# nuc120.net
KiCad netlist of a schematic drawn in Altium Designer
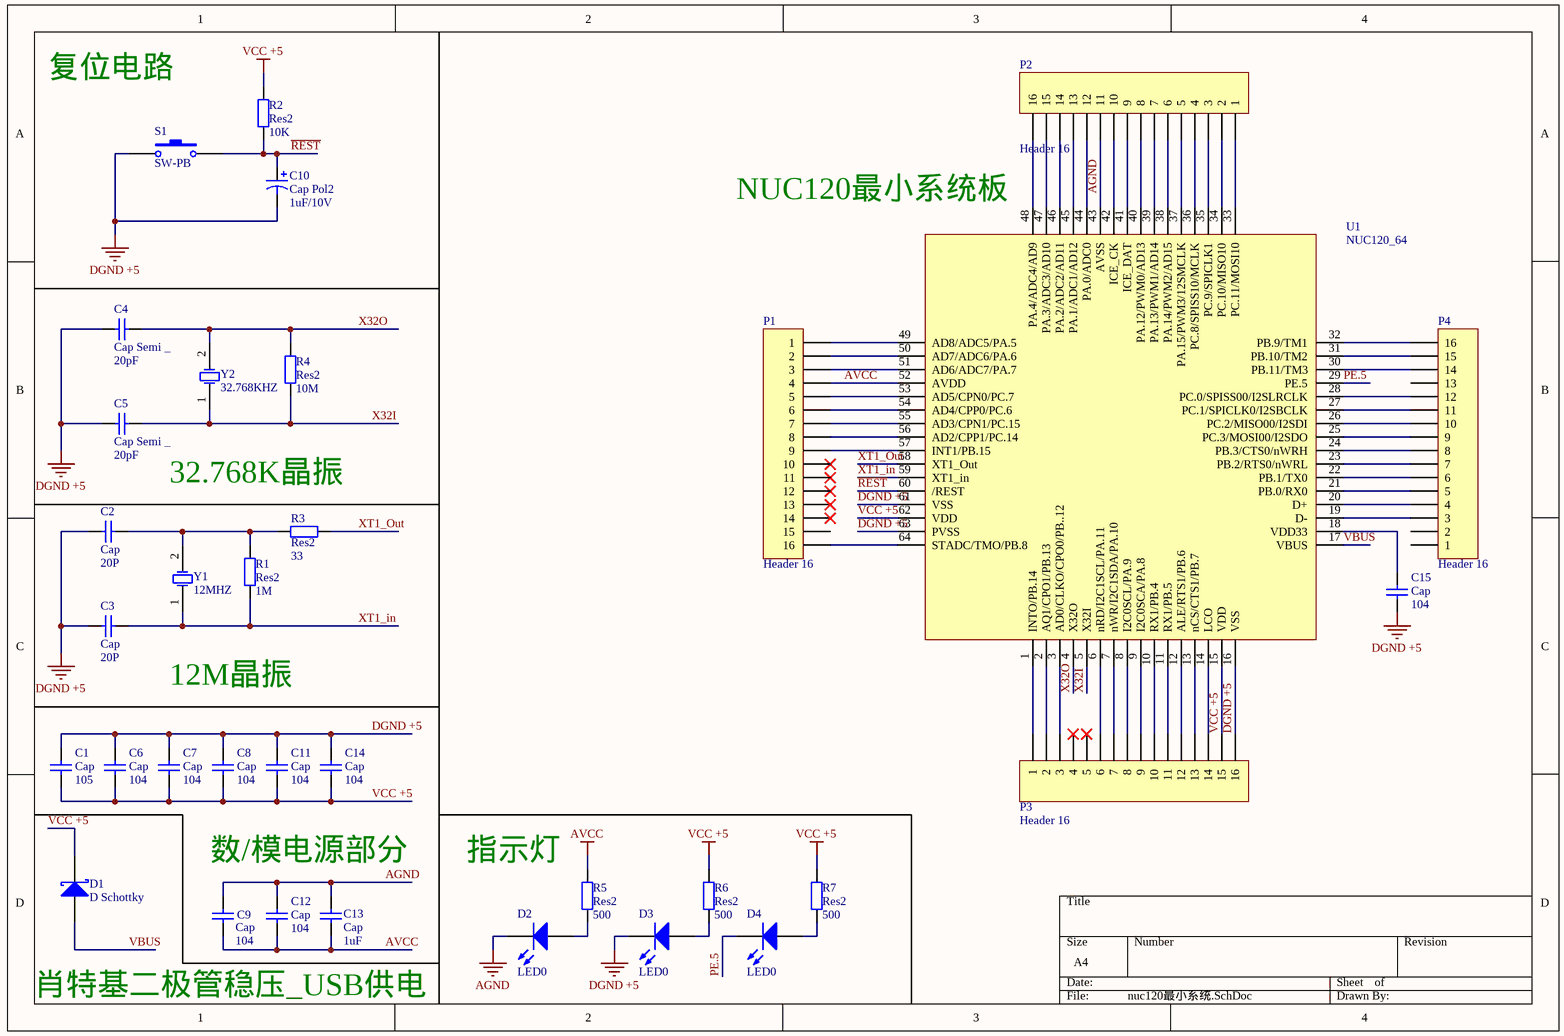
[diagram p0: nuc120最小系统.SchDoc]

(export (version "E")
  (design (tool "Eeschema 10.0.6"))
  (components
    (comp (ref "C1")
      (value "Cap")
      (footprint "1608[0603]")
      (description "Capacitor")
      (fields (field (name "ALTIUM_VALUE") "105") (field (name "PUBLISHER") "Altium Limited"))
      (libsource (lib "Miscellaneous Devices") (part "Cap"))
    )
    (comp (ref "C2")
      (value "Cap")
      (footprint "1608[0603]")
      (description "Capacitor")
      (fields (field (name "ALTIUM_VALUE") "20P") (field (name "PUBLISHER") "Altium Limited"))
      (libsource (lib "Miscellaneous Devices") (part "Cap"))
    )
    (comp (ref "C3")
      (value "Cap")
      (footprint "1608[0603]")
      (description "Capacitor")
      (fields (field (name "ALTIUM_VALUE") "20P") (field (name "PUBLISHER") "Altium Limited"))
      (libsource (lib "Miscellaneous Devices") (part "Cap"))
    )
    (comp (ref "C4")
      (value "Cap Semi _")
      (footprint "1608[0603]")
      (description "Capacitor (Semiconductor SIM Model)")
      (fields (field (name "ALTIUM_VALUE") "20pF") (field (name "PUBLISHER") "Altium Limited"))
      (libsource (lib "自制Miscellaneous Devices库") (part "Cap Semi _"))
    )
    (comp (ref "C5")
      (value "Cap Semi _")
      (footprint "1608[0603]")
      (description "Capacitor (Semiconductor SIM Model)")
      (fields (field (name "ALTIUM_VALUE") "20pF") (field (name "PUBLISHER") "Altium Limited"))
      (libsource (lib "自制Miscellaneous Devices库") (part "Cap Semi _"))
    )
    (comp (ref "C6")
      (value "Cap")
      (footprint "1608[0603]")
      (description "Capacitor")
      (fields (field (name "ALTIUM_VALUE") "104") (field (name "PUBLISHER") "Altium Limited"))
      (libsource (lib "Miscellaneous Devices") (part "Cap"))
    )
    (comp (ref "C7")
      (value "Cap")
      (footprint "1608[0603]")
      (description "Capacitor")
      (fields (field (name "ALTIUM_VALUE") "104") (field (name "PUBLISHER") "Altium Limited"))
      (libsource (lib "Miscellaneous Devices") (part "Cap"))
    )
    (comp (ref "C8")
      (value "Cap")
      (footprint "1608[0603]")
      (description "Capacitor")
      (fields (field (name "ALTIUM_VALUE") "104") (field (name "PUBLISHER") "Altium Limited"))
      (libsource (lib "Miscellaneous Devices") (part "Cap"))
    )
    (comp (ref "C9")
      (value "Cap")
      (footprint "1608[0603]")
      (description "Capacitor")
      (fields (field (name "ALTIUM_VALUE") "104") (field (name "PUBLISHER") "Altium Limited"))
      (libsource (lib "Miscellaneous Devices") (part "Cap"))
    )
    (comp (ref "C10")
      (value "Cap Pol2")
      (footprint "1608[0603]")
      (description "Polarized Capacitor (Axial)")
      (fields (field (name "ALTIUM_VALUE") "1uF/10V") (field (name "PUBLISHER") "Altium Limited"))
      (libsource (lib "自制Miscellaneous Devices库") (part "Cap Pol2"))
    )
    (comp (ref "C11")
      (value "Cap")
      (footprint "1608[0603]")
      (description "Capacitor")
      (fields (field (name "ALTIUM_VALUE") "104") (field (name "PUBLISHER") "Altium Limited"))
      (libsource (lib "Miscellaneous Devices") (part "Cap"))
    )
    (comp (ref "C12")
      (value "Cap")
      (footprint "1608[0603]")
      (description "Capacitor")
      (fields (field (name "ALTIUM_VALUE") "104") (field (name "PUBLISHER") "Altium Limited"))
      (libsource (lib "Miscellaneous Devices") (part "Cap"))
    )
    (comp (ref "C13")
      (value "Cap")
      (footprint "1608[0603]")
      (description "Capacitor")
      (fields (field (name "ALTIUM_VALUE") "1uF") (field (name "PUBLISHER") "Altium Limited"))
      (libsource (lib "Miscellaneous Devices") (part "Cap"))
    )
    (comp (ref "C14")
      (value "Cap")
      (footprint "1608[0603]")
      (description "Capacitor")
      (fields (field (name "ALTIUM_VALUE") "104") (field (name "PUBLISHER") "Altium Limited"))
      (libsource (lib "Miscellaneous Devices") (part "Cap"))
    )
    (comp (ref "C15")
      (value "Cap")
      (footprint "1608[0603]")
      (description "Capacitor")
      (fields (field (name "ALTIUM_VALUE") "104") (field (name "PUBLISHER") "Altium Limited"))
      (libsource (lib "Miscellaneous Devices") (part "Cap"))
    )
    (comp (ref "D1")
      (value "D Schottky")
      (footprint "SMB")
      (description "Schottky Diode")
      (fields (field (name "PUBLISHER") "Altium Limited"))
      (libsource (lib "Miscellaneous Devices") (part "D Schottky"))
    )
    (comp (ref "D2")
      (value "LED0")
      (footprint "0805")
      (description "Typical INFRARED GaAs LED")
      (fields (field (name "PUBLISHER") "Altium Limited"))
      (libsource (lib "Miscellaneous Devices") (part "LED0"))
    )
    (comp (ref "D3")
      (value "LED0")
      (footprint "0805")
      (description "Typical INFRARED GaAs LED")
      (fields (field (name "PUBLISHER") "Altium Limited"))
      (libsource (lib "Miscellaneous Devices") (part "LED0"))
    )
    (comp (ref "D4")
      (value "LED0")
      (footprint "0805")
      (description "Typical INFRARED GaAs LED")
      (fields (field (name "PUBLISHER") "Altium Limited"))
      (libsource (lib "Miscellaneous Devices") (part "LED0"))
    )
    (comp (ref "P1")
      (value "Header 16")
      (footprint "HDR2X8")
      (description "Header, 16-Pin")
      (fields (field (name "PUBLISHER") "Altium Limited"))
      (libsource (lib "") (part "Header 16_2"))
    )
    (comp (ref "P2")
      (value "Header 16")
      (footprint "HDR2X8")
      (description "Header, 16-Pin")
      (fields (field (name "PUBLISHER") "Altium Limited"))
      (libsource (lib "") (part "Header 16_1"))
    )
    (comp (ref "P3")
      (value "Header 16")
      (footprint "HDR2X8")
      (description "Header, 16-Pin")
      (fields (field (name "PUBLISHER") "Altium Limited"))
      (libsource (lib "自制Miscellaneous Connectors库") (part "Header 16"))
    )
    (comp (ref "P4")
      (value "Header 16")
      (footprint "HDR2X8")
      (description "Header, 16-Pin")
      (fields (field (name "PUBLISHER") "Altium Limited"))
      (libsource (lib "") (part "Header 16_3"))
    )
    (comp (ref "R1")
      (value "Res2")
      (footprint "1608[0603]")
      (description "Resistor")
      (fields (field (name "ALTIUM_VALUE") "1M") (field (name "PUBLISHER") "Altium Limited"))
      (libsource (lib "Miscellaneous Devices") (part "Res2"))
    )
    (comp (ref "R2")
      (value "Res2")
      (footprint "1608[0603]")
      (description "Resistor")
      (fields (field (name "ALTIUM_VALUE") "10K") (field (name "PUBLISHER") "Altium Limited"))
      (libsource (lib "自制Miscellaneous Devices库") (part "Res2"))
    )
    (comp (ref "R3")
      (value "Res2")
      (footprint "1608[0603]")
      (description "Resistor")
      (fields (field (name "ALTIUM_VALUE") "33") (field (name "PUBLISHER") "Altium Limited"))
      (libsource (lib "") (part "Res2_1"))
    )
    (comp (ref "R4")
      (value "Res2")
      (footprint "1608[0603]")
      (description "Resistor")
      (fields (field (name "ALTIUM_VALUE") "10M") (field (name "PUBLISHER") "Altium Limited"))
      (libsource (lib "自制Miscellaneous Devices库") (part "Res2"))
    )
    (comp (ref "R5")
      (value "Res2")
      (footprint "1608[0603]")
      (description "Resistor")
      (fields (field (name "ALTIUM_VALUE") "500") (field (name "PUBLISHER") "Altium Limited"))
      (libsource (lib "自制Miscellaneous Devices库") (part "Res2"))
    )
    (comp (ref "R6")
      (value "Res2")
      (footprint "1608[0603]")
      (description "Resistor")
      (fields (field (name "ALTIUM_VALUE") "500") (field (name "PUBLISHER") "Altium Limited"))
      (libsource (lib "自制Miscellaneous Devices库") (part "Res2"))
    )
    (comp (ref "R7")
      (value "Res2")
      (footprint "1608[0603]")
      (description "Resistor")
      (fields (field (name "ALTIUM_VALUE") "500") (field (name "PUBLISHER") "Altium Limited"))
      (libsource (lib "自制Miscellaneous Devices库") (part "Res2"))
    )
    (comp (ref "S1")
      (value "SW-PB")
      (footprint "SW_PB4_SMD")
      (description "Switch")
      (fields (field (name "PUBLISHER") "Altium Limited"))
      (libsource (lib "自制Miscellaneous Devices库") (part "SW-PB"))
    )
    (comp (ref "U1")
      (value "NUC120_64")
      (footprint "PCBComponent_1")
      (libsource (lib "自制原理图元件库") (part "NUC120_64"))
    )
    (comp (ref "Y1")
      (value "12MHZ")
      (footprint "XTAL_SMD")
      (description "Crystal Oscillator")
      (fields (field (name "PUBLISHER") "Altium Limited"))
      (libsource (lib "自制Miscellaneous Devices库") (part "XTAL"))
    )
    (comp (ref "Y2")
      (value "32.768KHZ")
      (footprint "XTAL_SMD")
      (description "Crystal Oscillator")
      (fields (field (name "PUBLISHER") "Altium Limited"))
      (libsource (lib "自制Miscellaneous Devices库") (part "XTAL"))
    )
  )
  (nets
    (net (code "1") (name "/PE.5") (class "Default")
      (node (ref "D4") (pin "2") (pinfunction "K_2") (pintype "passive"))
      (node (ref "U1") (pin "29") (pinfunction "PE.5_29") (pintype "passive"))
    )
    (net (code "2") (name "/VBUS") (class "Default")
      (node (ref "D1") (pin "1") (pinfunction "A_1") (pintype "passive"))
      (node (ref "U1") (pin "17") (pinfunction "VBUS_17") (pintype "passive"))
    )
    (net (code "3") (name "/X32I") (class "Default")
      (node (ref "C5") (pin "2") (pinfunction "2_2") (pintype "passive"))
      (node (ref "R4") (pin "1") (pinfunction "1_1") (pintype "passive"))
      (node (ref "U1") (pin "5") (pinfunction "X32I_5") (pintype "passive"))
      (node (ref "Y2") (pin "1") (pinfunction "OSC1_1") (pintype "passive"))
    )
    (net (code "4") (name "/X32O") (class "Default")
      (node (ref "C4") (pin "2") (pinfunction "2_2") (pintype "passive"))
      (node (ref "R4") (pin "2") (pinfunction "2_2") (pintype "passive"))
      (node (ref "U1") (pin "4") (pinfunction "X32O_4") (pintype "passive"))
      (node (ref "Y2") (pin "2") (pinfunction "OSC2_2") (pintype "passive"))
    )
    (net (code "5") (name "/XT1_Out") (class "Default")
      (node (ref "R3") (pin "1") (pinfunction "1_1") (pintype "passive"))
      (node (ref "U1") (pin "58") (pinfunction "XT1_Out_58") (pintype "passive"))
    )
    (net (code "6") (name "/XT1_in") (class "Default")
      (node (ref "C3") (pin "2") (pinfunction "2_2") (pintype "passive"))
      (node (ref "R1") (pin "1") (pinfunction "1_1") (pintype "passive"))
      (node (ref "U1") (pin "59") (pinfunction "XT1_in_59") (pintype "passive"))
      (node (ref "Y1") (pin "1") (pinfunction "OSC1_1") (pintype "passive"))
    )
    (net (code "7") (name "/~{REST}") (class "Default")
      (node (ref "C10") (pin "1") (pinfunction "1_1") (pintype "passive"))
      (node (ref "R2") (pin "1") (pinfunction "1_1") (pintype "passive"))
      (node (ref "S1") (pin "2") (pinfunction "2_2") (pintype "passive"))
      (node (ref "U1") (pin "60") (pinfunction "/REST_60") (pintype "passive"))
    )
    (net (code "8") (name "AGND") (class "Default")
      (node (ref "C12") (pin "1") (pinfunction "1_1") (pintype "passive"))
      (node (ref "C13") (pin "1") (pinfunction "1_1") (pintype "passive"))
      (node (ref "C9") (pin "1") (pinfunction "1_1") (pintype "passive"))
      (node (ref "D2") (pin "2") (pinfunction "K_2") (pintype "passive"))
      (node (ref "P2") (pin "11") (pinfunction "11_11") (pintype "passive"))
      (node (ref "U1") (pin "43") (pinfunction "AVSS_43") (pintype "passive"))
    )
    (net (code "9") (name "AVCC") (class "Default")
      (node (ref "C12") (pin "2") (pinfunction "2_2") (pintype "passive"))
      (node (ref "C13") (pin "2") (pinfunction "2_2") (pintype "passive"))
      (node (ref "C9") (pin "2") (pinfunction "2_2") (pintype "passive"))
      (node (ref "P1") (pin "4") (pinfunction "4_4") (pintype "passive"))
      (node (ref "R5") (pin "2") (pinfunction "2_2") (pintype "passive"))
      (node (ref "U1") (pin "52") (pinfunction "AVDD_52") (pintype "passive"))
    )
    (net (code "10") (name "DGND +5") (class "Default")
      (node (ref "C1") (pin "1") (pinfunction "1_1") (pintype "passive"))
      (node (ref "C10") (pin "2") (pinfunction "2_2") (pintype "passive"))
      (node (ref "C11") (pin "1") (pinfunction "1_1") (pintype "passive"))
      (node (ref "C14") (pin "1") (pinfunction "1_1") (pintype "passive"))
      (node (ref "C15") (pin "2") (pinfunction "2_2") (pintype "passive"))
      (node (ref "C2") (pin "1") (pinfunction "1_1") (pintype "passive"))
      (node (ref "C3") (pin "1") (pinfunction "1_1") (pintype "passive"))
      (node (ref "C4") (pin "1") (pinfunction "1_1") (pintype "passive"))
      (node (ref "C5") (pin "1") (pinfunction "1_1") (pintype "passive"))
      (node (ref "C6") (pin "1") (pinfunction "1_1") (pintype "passive"))
      (node (ref "C7") (pin "1") (pinfunction "1_1") (pintype "passive"))
      (node (ref "C8") (pin "1") (pinfunction "1_1") (pintype "passive"))
      (node (ref "D3") (pin "2") (pinfunction "K_2") (pintype "passive"))
      (node (ref "P3") (pin "16") (pinfunction "16_16") (pintype "passive"))
      (node (ref "S1") (pin "1") (pinfunction "1_1") (pintype "passive"))
      (node (ref "U1") (pin "16") (pinfunction "VSS_16") (pintype "passive"))
      (node (ref "U1") (pin "61") (pinfunction "VSS_61") (pintype "passive"))
      (node (ref "U1") (pin "63") (pinfunction "PVSS_63") (pintype "passive"))
    )
    (net (code "11") (name "Net-(D2-A)") (class "Default")
      (node (ref "D2") (pin "1") (pinfunction "A_1") (pintype "passive"))
      (node (ref "R5") (pin "1") (pinfunction "1_1") (pintype "passive"))
    )
    (net (code "12") (name "Net-(D3-A)") (class "Default")
      (node (ref "D3") (pin "1") (pinfunction "A_1") (pintype "passive"))
      (node (ref "R6") (pin "1") (pinfunction "1_1") (pintype "passive"))
    )
    (net (code "13") (name "Net-(D4-A)") (class "Default")
      (node (ref "D4") (pin "1") (pinfunction "A_1") (pintype "passive"))
      (node (ref "R7") (pin "1") (pinfunction "1_1") (pintype "passive"))
    )
    (net (code "14") (name "Net-(U1-AD0{slash}CLKO{slash}CPO0{slash}PB..12)") (class "Default")
      (node (ref "P3") (pin "3") (pinfunction "3_3") (pintype "passive"))
      (node (ref "U1") (pin "3") (pinfunction "AD0/CLKO/CPO0/PB..12_3") (pintype "passive"))
    )
    (net (code "15") (name "Net-(U1-AD2{slash}CPP1{slash}PC.14)") (class "Default")
      (node (ref "P1") (pin "8") (pinfunction "8_8") (pintype "passive"))
      (node (ref "U1") (pin "56") (pinfunction "AD2/CPP1/PC.14_56") (pintype "passive"))
    )
    (net (code "16") (name "Net-(U1-AD3{slash}CPN1{slash}PC.15)") (class "Default")
      (node (ref "P1") (pin "7") (pinfunction "7_7") (pintype "passive"))
      (node (ref "U1") (pin "55") (pinfunction "AD3/CPN1/PC.15_55") (pintype "passive"))
    )
    (net (code "17") (name "Net-(U1-AD4{slash}CPP0{slash}PC.6)") (class "Default")
      (node (ref "P1") (pin "6") (pinfunction "6_6") (pintype "passive"))
      (node (ref "U1") (pin "54") (pinfunction "AD4/CPP0/PC.6_54") (pintype "passive"))
    )
    (net (code "18") (name "Net-(U1-AD5{slash}CPN0{slash}PC.7)") (class "Default")
      (node (ref "P1") (pin "5") (pinfunction "5_5") (pintype "passive"))
      (node (ref "U1") (pin "53") (pinfunction "AD5/CPN0/PC.7_53") (pintype "passive"))
    )
    (net (code "19") (name "Net-(U1-AD6{slash}ADC7{slash}PA.7)") (class "Default")
      (node (ref "P1") (pin "3") (pinfunction "3_3") (pintype "passive"))
      (node (ref "U1") (pin "51") (pinfunction "AD6/ADC7/PA.7_51") (pintype "passive"))
    )
    (net (code "20") (name "Net-(U1-AD7{slash}ADC6{slash}PA.6)") (class "Default")
      (node (ref "P1") (pin "2") (pinfunction "2_2") (pintype "passive"))
      (node (ref "U1") (pin "50") (pinfunction "AD7/ADC6/PA.6_50") (pintype "passive"))
    )
    (net (code "21") (name "Net-(U1-AD8{slash}ADC5{slash}PA.5)") (class "Default")
      (node (ref "P1") (pin "1") (pinfunction "1_1") (pintype "passive"))
      (node (ref "U1") (pin "49") (pinfunction "AD8/ADC5/PA.5_49") (pintype "passive"))
    )
    (net (code "22") (name "Net-(U1-ALE{slash}RTS1{slash}PB.6)") (class "Default")
      (node (ref "P3") (pin "12") (pinfunction "12_12") (pintype "passive"))
      (node (ref "U1") (pin "12") (pinfunction "ALE/RTS1/PB.6_12") (pintype "passive"))
    )
    (net (code "23") (name "Net-(U1-AQ1{slash}CPO1{slash}PB.13)") (class "Default")
      (node (ref "P3") (pin "2") (pinfunction "2_2") (pintype "passive"))
      (node (ref "U1") (pin "2") (pinfunction "AQ1/CPO1/PB.13_2") (pintype "passive"))
    )
    (net (code "24") (name "Net-(U1-D+)") (class "Default")
      (node (ref "P4") (pin "4") (pinfunction "4_4") (pintype "passive"))
      (node (ref "U1") (pin "20") (pinfunction "D+_20") (pintype "passive"))
    )
    (net (code "25") (name "Net-(U1-D-)") (class "Default")
      (node (ref "P4") (pin "3") (pinfunction "3_3") (pintype "passive"))
      (node (ref "U1") (pin "19") (pinfunction "D-_19") (pintype "passive"))
    )
    (net (code "26") (name "Net-(U1-I2C0SCA{slash}PA.8)") (class "Default")
      (node (ref "P3") (pin "9") (pinfunction "9_9") (pintype "passive"))
      (node (ref "U1") (pin "9") (pinfunction "I2C0SCA/PA.8_9") (pintype "passive"))
    )
    (net (code "27") (name "Net-(U1-I2C0SCL{slash}PA.9)") (class "Default")
      (node (ref "P3") (pin "8") (pinfunction "8_8") (pintype "passive"))
      (node (ref "U1") (pin "8") (pinfunction "I2C0SCL/PA.9_8") (pintype "passive"))
    )
    (net (code "28") (name "Net-(U1-ICE_CK)") (class "Default")
      (node (ref "P2") (pin "10") (pinfunction "10_10") (pintype "passive"))
      (node (ref "U1") (pin "42") (pinfunction "ICE_CK_42") (pintype "passive"))
    )
    (net (code "29") (name "Net-(U1-ICE_DAT)") (class "Default")
      (node (ref "P2") (pin "9") (pinfunction "9_9") (pintype "passive"))
      (node (ref "U1") (pin "41") (pinfunction "ICE_DAT_41") (pintype "passive"))
    )
    (net (code "30") (name "Net-(U1-INT1{slash}PB.15)") (class "Default")
      (node (ref "P1") (pin "9") (pinfunction "9_9") (pintype "passive"))
      (node (ref "U1") (pin "57") (pinfunction "INT1/PB.15_57") (pintype "passive"))
    )
    (net (code "31") (name "Net-(U1-INTO{slash}PB.14)") (class "Default")
      (node (ref "P3") (pin "1") (pinfunction "1_1") (pintype "passive"))
      (node (ref "U1") (pin "1") (pinfunction "INTO/PB.14_1") (pintype "passive"))
    )
    (net (code "32") (name "Net-(U1-LCO)") (class "Default")
      (node (ref "P3") (pin "14") (pinfunction "14_14") (pintype "passive"))
      (node (ref "U1") (pin "14") (pinfunction "LCO_14") (pintype "passive"))
    )
    (net (code "33") (name "Net-(U1-PA.0{slash}ADC0)") (class "Default")
      (node (ref "P2") (pin "12") (pinfunction "12_12") (pintype "passive"))
      (node (ref "U1") (pin "44") (pinfunction "PA.0/ADC0_44") (pintype "passive"))
    )
    (net (code "34") (name "Net-(U1-PA.1{slash}ADC1{slash}AD12)") (class "Default")
      (node (ref "P2") (pin "13") (pinfunction "13_13") (pintype "passive"))
      (node (ref "U1") (pin "45") (pinfunction "PA.1/ADC1/AD12_45") (pintype "passive"))
    )
    (net (code "35") (name "Net-(U1-PA.2{slash}ADC2{slash}AD11)") (class "Default")
      (node (ref "P2") (pin "14") (pinfunction "14_14") (pintype "passive"))
      (node (ref "U1") (pin "46") (pinfunction "PA.2/ADC2/AD11_46") (pintype "passive"))
    )
    (net (code "36") (name "Net-(U1-PA.3{slash}ADC3{slash}AD10)") (class "Default")
      (node (ref "P2") (pin "15") (pinfunction "15_15") (pintype "passive"))
      (node (ref "U1") (pin "47") (pinfunction "PA.3/ADC3/AD10_47") (pintype "passive"))
    )
    (net (code "37") (name "Net-(U1-PA.4{slash}ADC4{slash}AD9)") (class "Default")
      (node (ref "P2") (pin "16") (pinfunction "16_16") (pintype "passive"))
      (node (ref "U1") (pin "48") (pinfunction "PA.4/ADC4/AD9_48") (pintype "passive"))
    )
    (net (code "38") (name "Net-(U1-PA.12{slash}PWM0{slash}AD13)") (class "Default")
      (node (ref "P2") (pin "8") (pinfunction "8_8") (pintype "passive"))
      (node (ref "U1") (pin "40") (pinfunction "PA.12/PWM0/AD13_40") (pintype "passive"))
    )
    (net (code "39") (name "Net-(U1-PA.13{slash}PWM1{slash}AD14)") (class "Default")
      (node (ref "P2") (pin "7") (pinfunction "7_7") (pintype "passive"))
      (node (ref "U1") (pin "39") (pinfunction "PA.13/PWM1/AD14_39") (pintype "passive"))
    )
    (net (code "40") (name "Net-(U1-PA.14{slash}PWM2{slash}AD15)") (class "Default")
      (node (ref "P2") (pin "6") (pinfunction "6_6") (pintype "passive"))
      (node (ref "U1") (pin "38") (pinfunction "PA.14/PWM2/AD15_38") (pintype "passive"))
    )
    (net (code "41") (name "Net-(U1-PA.15{slash}PWM3{slash}12SMCLK)") (class "Default")
      (node (ref "P2") (pin "5") (pinfunction "5_5") (pintype "passive"))
      (node (ref "U1") (pin "37") (pinfunction "PA.15/PWM3/12SMCLK_37") (pintype "passive"))
    )
    (net (code "42") (name "Net-(U1-PB.0{slash}RX0)") (class "Default")
      (node (ref "P4") (pin "5") (pinfunction "5_5") (pintype "passive"))
      (node (ref "U1") (pin "21") (pinfunction "PB.0/RX0_21") (pintype "passive"))
    )
    (net (code "43") (name "Net-(U1-PB.1{slash}TX0)") (class "Default")
      (node (ref "P4") (pin "6") (pinfunction "6_6") (pintype "passive"))
      (node (ref "U1") (pin "22") (pinfunction "PB.1/TX0_22") (pintype "passive"))
    )
    (net (code "44") (name "Net-(U1-PB.2{slash}RTS0{slash}nWRL)") (class "Default")
      (node (ref "P4") (pin "7") (pinfunction "7_7") (pintype "passive"))
      (node (ref "U1") (pin "23") (pinfunction "PB.2/RTS0/nWRL_23") (pintype "passive"))
    )
    (net (code "45") (name "Net-(U1-PB.3{slash}CTS0{slash}nWRH)") (class "Default")
      (node (ref "P4") (pin "8") (pinfunction "8_8") (pintype "passive"))
      (node (ref "U1") (pin "24") (pinfunction "PB.3/CTS0/nWRH_24") (pintype "passive"))
    )
    (net (code "46") (name "Net-(U1-PB.9{slash}TM1)") (class "Default")
      (node (ref "P4") (pin "16") (pinfunction "16_16") (pintype "passive"))
      (node (ref "U1") (pin "32") (pinfunction "PB.9/TM1_32") (pintype "passive"))
    )
    (net (code "47") (name "Net-(U1-PB.10{slash}TM2)") (class "Default")
      (node (ref "P4") (pin "15") (pinfunction "15_15") (pintype "passive"))
      (node (ref "U1") (pin "31") (pinfunction "PB.10/TM2_31") (pintype "passive"))
    )
    (net (code "48") (name "Net-(U1-PB.11{slash}TM3)") (class "Default")
      (node (ref "P4") (pin "14") (pinfunction "14_14") (pintype "passive"))
      (node (ref "U1") (pin "30") (pinfunction "PB.11/TM3_30") (pintype "passive"))
    )
    (net (code "49") (name "Net-(U1-PC.0{slash}SPISS00{slash}I2SLRCLK)") (class "Default")
      (node (ref "P4") (pin "12") (pinfunction "12_12") (pintype "passive"))
      (node (ref "U1") (pin "28") (pinfunction "PC.0/SPISS00/I2SLRCLK_28") (pintype "passive"))
    )
    (net (code "50") (name "Net-(U1-PC.1{slash}SPICLK0{slash}I2SBCLK)") (class "Default")
      (node (ref "P4") (pin "11") (pinfunction "11_11") (pintype "passive"))
      (node (ref "U1") (pin "27") (pinfunction "PC.1/SPICLK0/I2SBCLK_27") (pintype "passive"))
    )
    (net (code "51") (name "Net-(U1-PC.2{slash}MISO00{slash}I2SDI)") (class "Default")
      (node (ref "P4") (pin "10") (pinfunction "10_10") (pintype "passive"))
      (node (ref "U1") (pin "26") (pinfunction "PC.2/MISO00/I2SDI_26") (pintype "passive"))
    )
    (net (code "52") (name "Net-(U1-PC.3{slash}MOSI00{slash}I2SDO)") (class "Default")
      (node (ref "P4") (pin "9") (pinfunction "9_9") (pintype "passive"))
      (node (ref "U1") (pin "25") (pinfunction "PC.3/MOSI00/I2SDO_25") (pintype "passive"))
    )
    (net (code "53") (name "Net-(U1-PC.8{slash}SPISS10{slash}MCLK)") (class "Default")
      (node (ref "P2") (pin "4") (pinfunction "4_4") (pintype "passive"))
      (node (ref "U1") (pin "36") (pinfunction "PC.8/SPISS10/MCLK_36") (pintype "passive"))
    )
    (net (code "54") (name "Net-(U1-PC.9{slash}SPICLK1)") (class "Default")
      (node (ref "P2") (pin "3") (pinfunction "3_3") (pintype "passive"))
      (node (ref "U1") (pin "35") (pinfunction "PC.9/SPICLK1_35") (pintype "passive"))
    )
    (net (code "55") (name "Net-(U1-PC.10{slash}MISO10)") (class "Default")
      (node (ref "P2") (pin "2") (pinfunction "2_2") (pintype "passive"))
      (node (ref "U1") (pin "34") (pinfunction "PC.10/MISO10_34") (pintype "passive"))
    )
    (net (code "56") (name "Net-(U1-PC.11{slash}MOSI10)") (class "Default")
      (node (ref "P2") (pin "1") (pinfunction "1_1") (pintype "passive"))
      (node (ref "U1") (pin "33") (pinfunction "PC.11/MOSI10_33") (pintype "passive"))
    )
    (net (code "57") (name "Net-(U1-RX1{slash}PB.4)") (class "Default")
      (node (ref "P3") (pin "10") (pinfunction "10_10") (pintype "passive"))
      (node (ref "U1") (pin "10") (pinfunction "RX1/PB.4_10") (pintype "passive"))
    )
    (net (code "58") (name "Net-(U1-RX1{slash}PB.5)") (class "Default")
      (node (ref "P3") (pin "11") (pinfunction "11_11") (pintype "passive"))
      (node (ref "U1") (pin "11") (pinfunction "RX1/PB.5_11") (pintype "passive"))
    )
    (net (code "59") (name "Net-(U1-STADC{slash}TMO{slash}PB.8)") (class "Default")
      (node (ref "P1") (pin "16") (pinfunction "16_16") (pintype "passive"))
      (node (ref "U1") (pin "64") (pinfunction "STADC/TMO/PB.8_64") (pintype "passive"))
    )
    (net (code "60") (name "Net-(U1-VDD33)") (class "Default")
      (node (ref "C15") (pin "1") (pinfunction "1_1") (pintype "passive"))
      (node (ref "U1") (pin "18") (pinfunction "VDD33_18") (pintype "passive"))
    )
    (net (code "61") (name "Net-(U1-nCS{slash}CTS1{slash}PB.7)") (class "Default")
      (node (ref "P3") (pin "13") (pinfunction "13_13") (pintype "passive"))
      (node (ref "U1") (pin "13") (pinfunction "nCS/CTS1/PB.7_13") (pintype "passive"))
    )
    (net (code "62") (name "Net-(U1-nRD{slash}I2C1SCL{slash}PA.11)") (class "Default")
      (node (ref "P3") (pin "6") (pinfunction "6_6") (pintype "passive"))
      (node (ref "U1") (pin "6") (pinfunction "nRD/I2C1SCL/PA.11_6") (pintype "passive"))
    )
    (net (code "63") (name "Net-(U1-nWR{slash}I2C1SDA{slash}PA.10)") (class "Default")
      (node (ref "P3") (pin "7") (pinfunction "7_7") (pintype "passive"))
      (node (ref "U1") (pin "7") (pinfunction "nWR/I2C1SDA/PA.10_7") (pintype "passive"))
    )
    (net (code "64") (name "Net-(Y1-OSC2)") (class "Default")
      (node (ref "C2") (pin "2") (pinfunction "2_2") (pintype "passive"))
      (node (ref "R1") (pin "2") (pinfunction "2_2") (pintype "passive"))
      (node (ref "R3") (pin "2") (pinfunction "2_2") (pintype "passive"))
      (node (ref "Y1") (pin "2") (pinfunction "OSC2_2") (pintype "passive"))
    )
    (net (code "65") (name "VCC +5") (class "Default")
      (node (ref "C1") (pin "2") (pinfunction "2_2") (pintype "passive"))
      (node (ref "C11") (pin "2") (pinfunction "2_2") (pintype "passive"))
      (node (ref "C14") (pin "2") (pinfunction "2_2") (pintype "passive"))
      (node (ref "C6") (pin "2") (pinfunction "2_2") (pintype "passive"))
      (node (ref "C7") (pin "2") (pinfunction "2_2") (pintype "passive"))
      (node (ref "C8") (pin "2") (pinfunction "2_2") (pintype "passive"))
      (node (ref "D1") (pin "2") (pinfunction "K_2") (pintype "passive"))
      (node (ref "P3") (pin "15") (pinfunction "15_15") (pintype "passive"))
      (node (ref "R2") (pin "2") (pinfunction "2_2") (pintype "passive"))
      (node (ref "R6") (pin "2") (pinfunction "2_2") (pintype "passive"))
      (node (ref "R7") (pin "2") (pinfunction "2_2") (pintype "passive"))
      (node (ref "U1") (pin "15") (pinfunction "VDD_15") (pintype "passive"))
      (node (ref "U1") (pin "62") (pinfunction "VDD_62") (pintype "passive"))
    )
    (net (code "66") (name "unconnected-(P1-Pad10)") (class "Default")
      (node (ref "P1") (pin "10") (pinfunction "10_10") (pintype "passive+no_connect"))
    )
    (net (code "67") (name "unconnected-(P1-Pad11)") (class "Default")
      (node (ref "P1") (pin "11") (pinfunction "11_11") (pintype "passive+no_connect"))
    )
    (net (code "68") (name "unconnected-(P1-Pad12)") (class "Default")
      (node (ref "P1") (pin "12") (pinfunction "12_12") (pintype "passive+no_connect"))
    )
    (net (code "69") (name "unconnected-(P1-Pad13)") (class "Default")
      (node (ref "P1") (pin "13") (pinfunction "13_13") (pintype "passive+no_connect"))
    )
    (net (code "70") (name "unconnected-(P1-Pad14)") (class "Default")
      (node (ref "P1") (pin "14") (pinfunction "14_14") (pintype "passive+no_connect"))
    )
    (net (code "71") (name "unconnected-(P1-Pad15)") (class "Default")
      (node (ref "P1") (pin "15") (pinfunction "15_15") (pintype "passive"))
    )
    (net (code "72") (name "unconnected-(P3-Pad4)") (class "Default")
      (node (ref "P3") (pin "4") (pinfunction "4_4") (pintype "passive+no_connect"))
    )
    (net (code "73") (name "unconnected-(P3-Pad5)") (class "Default")
      (node (ref "P3") (pin "5") (pinfunction "5_5") (pintype "passive+no_connect"))
    )
    (net (code "74") (name "unconnected-(P4-Pad1)") (class "Default")
      (node (ref "P4") (pin "1") (pinfunction "1_1") (pintype "passive"))
    )
    (net (code "75") (name "unconnected-(P4-Pad2)") (class "Default")
      (node (ref "P4") (pin "2") (pinfunction "2_2") (pintype "passive"))
    )
    (net (code "76") (name "unconnected-(P4-Pad13)") (class "Default")
      (node (ref "P4") (pin "13") (pinfunction "13_13") (pintype "passive"))
    )
  )
)
